# LPDDR4_SDRAM_1.net
KiCad netlist of a schematic drawn in Altium Designer
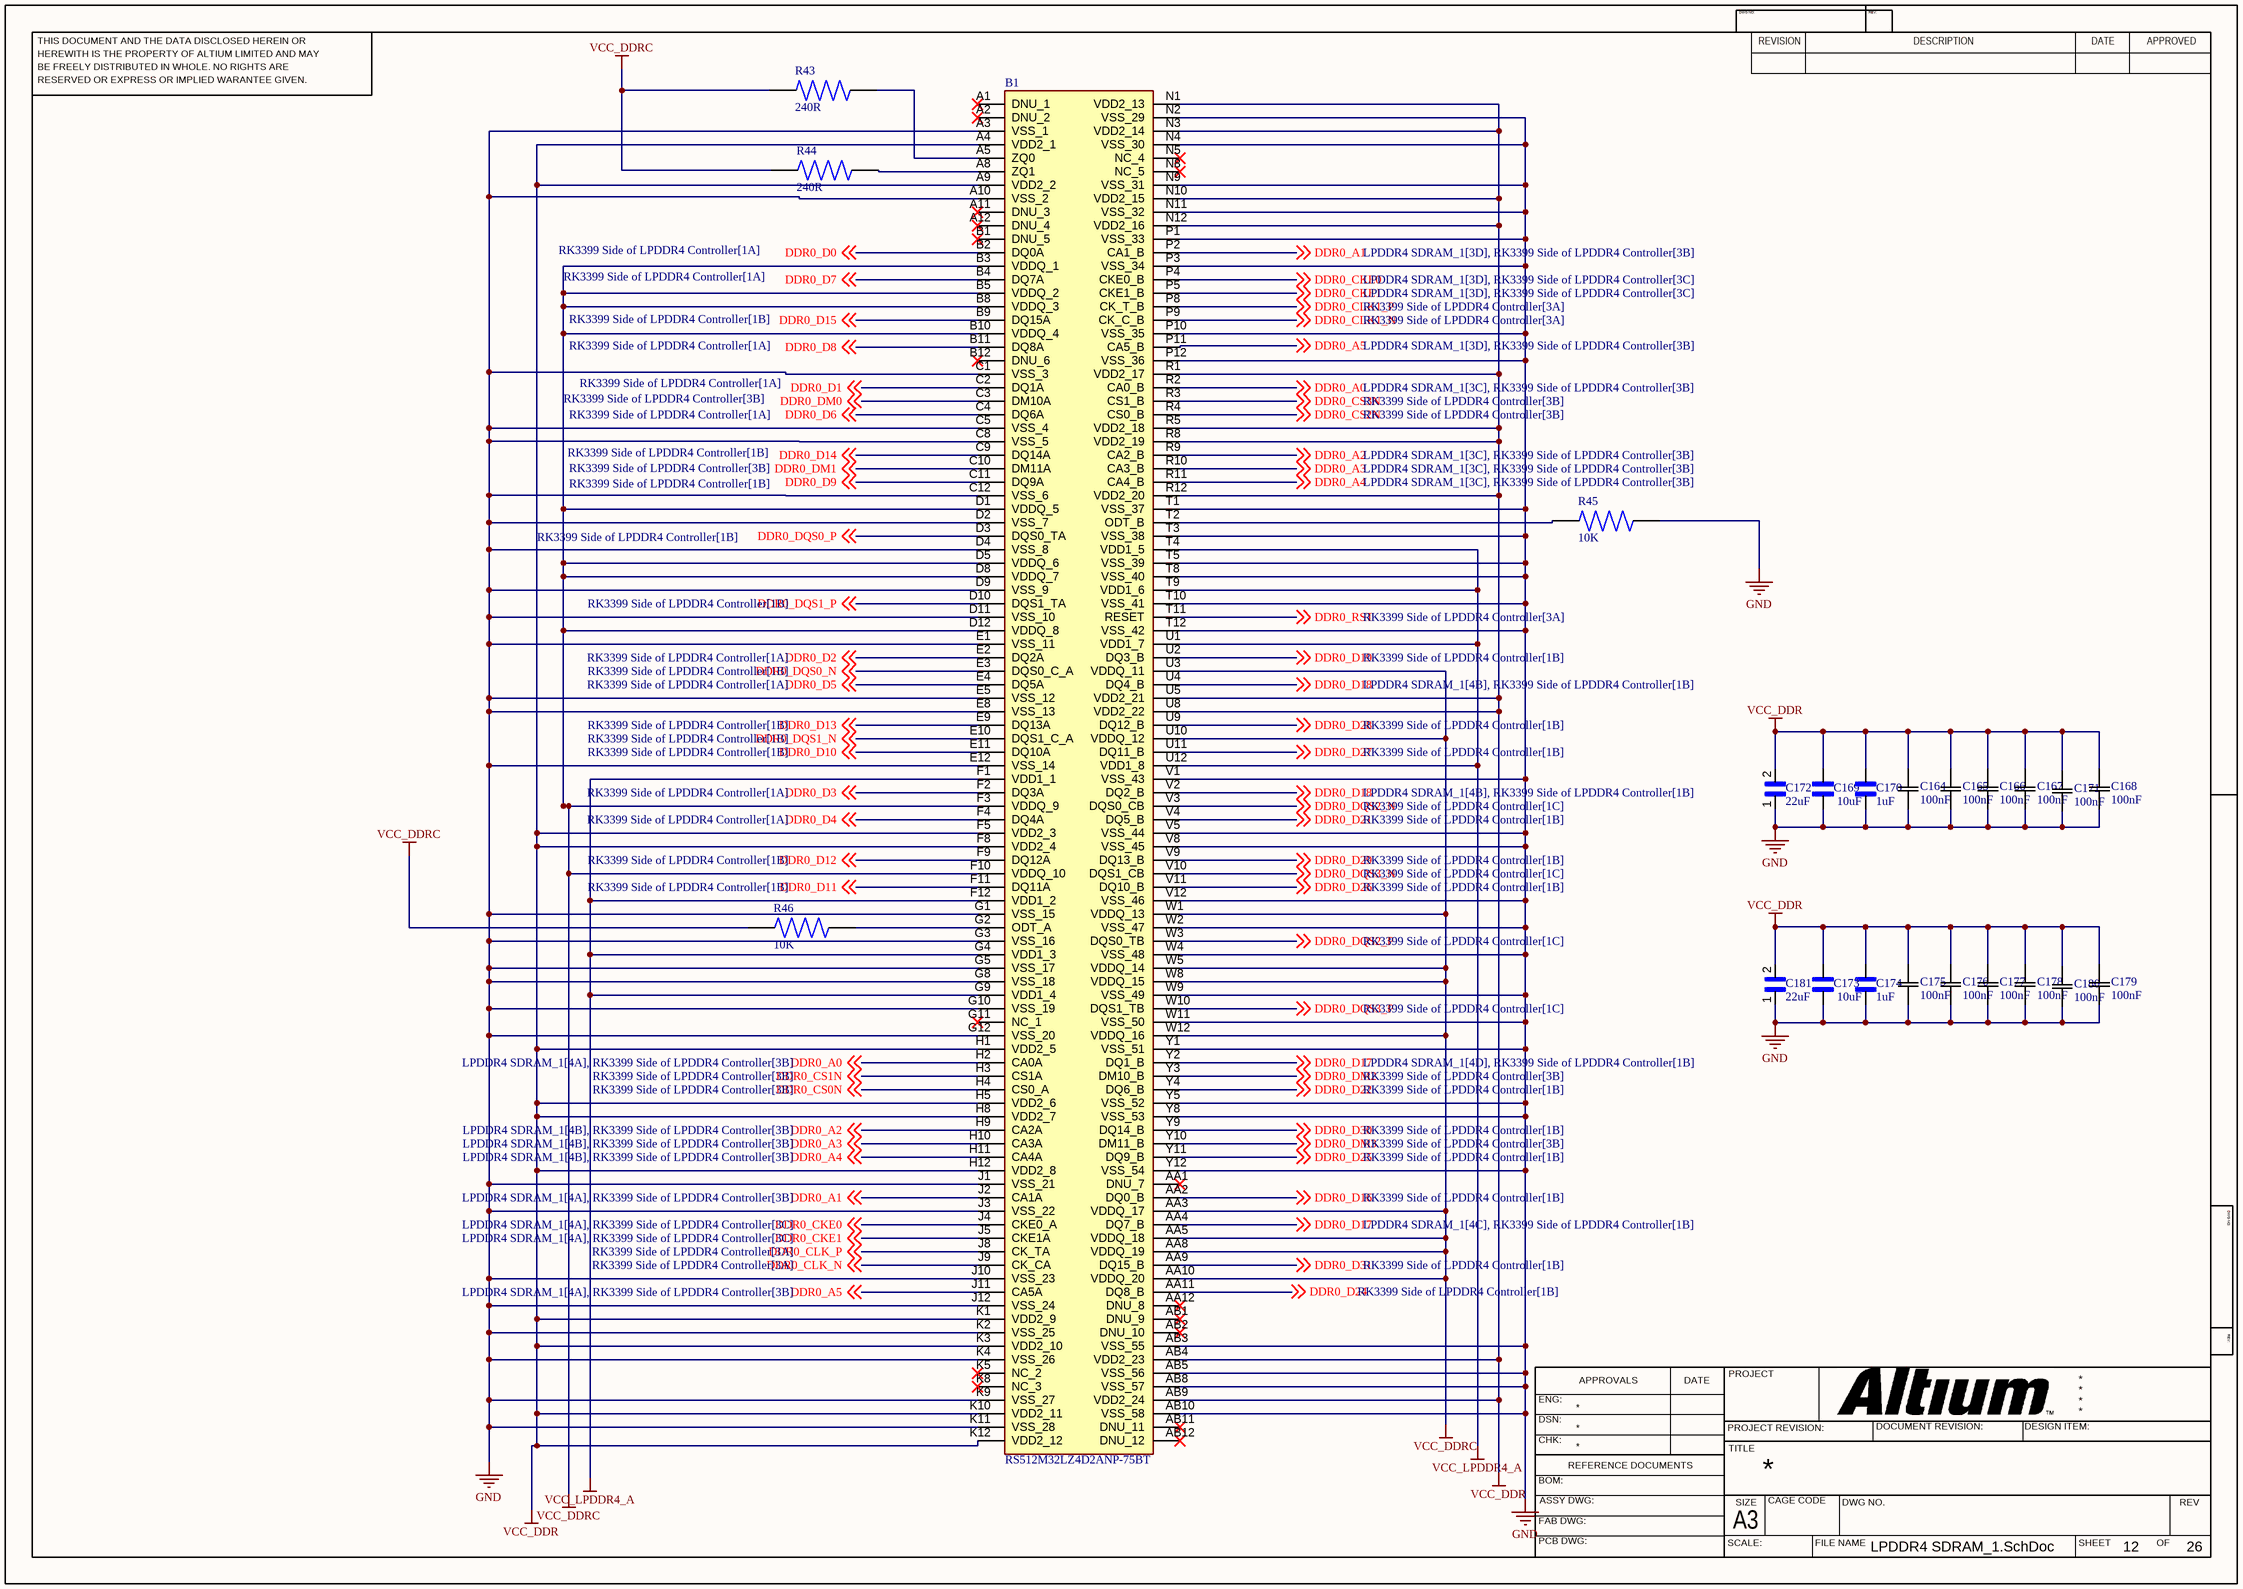
[diagram p0: LPDDR4 SDRAM_1.SchDoc]

(export (version "E")
  (design (tool "Eeschema 10.0.6"))
  (components
    (comp (ref "B1")
      (value "RS512M32LZ4D2ANP-75BT")
      (footprint "BGA200C65P12X22_1000X1500X100")
      (description "BGA-200 New Arrivals ROHS")
      (libsource (lib "RS512M32LZ4D2ANP-75BT") (part "RS512M32LZ4D2ANP-75BT"))
    )
    (comp (ref "C164")
      (value "100nF")
      (footprint "CAP_1005_TDK")
      (description "Description")
      (fields
        (field (name "MANUFACTURER_PART_NUMBER") "C1005X7R1H104M050BB")
        (field (name "COPYRIGHT") "Copyright (C) 2025 Ultra Librarian. All rights reserved.")
      )
      (libsource (lib "C1005X7R1H104M050BB") (part "C1005X7R1H104M050BB"))
    )
    (comp (ref "C165")
      (value "100nF")
      (footprint "CAP_1005_TDK")
      (description "Description")
      (fields
        (field (name "MANUFACTURER_PART_NUMBER") "C1005X7R1H104M050BB")
        (field (name "COPYRIGHT") "Copyright (C) 2025 Ultra Librarian. All rights reserved.")
      )
      (libsource (lib "C1005X7R1H104M050BB") (part "C1005X7R1H104M050BB"))
    )
    (comp (ref "C166")
      (value "100nF")
      (footprint "CAP_1005_TDK")
      (description "Description")
      (fields
        (field (name "MANUFACTURER_PART_NUMBER") "C1005X7R1H104M050BB")
        (field (name "COPYRIGHT") "Copyright (C) 2025 Ultra Librarian. All rights reserved.")
      )
      (libsource (lib "C1005X7R1H104M050BB") (part "C1005X7R1H104M050BB"))
    )
    (comp (ref "C167")
      (value "100nF")
      (footprint "CAP_1005_TDK")
      (description "Description")
      (fields
        (field (name "MANUFACTURER_PART_NUMBER") "C1005X7R1H104M050BB")
        (field (name "COPYRIGHT") "Copyright (C) 2025 Ultra Librarian. All rights reserved.")
      )
      (libsource (lib "C1005X7R1H104M050BB") (part "C1005X7R1H104M050BB"))
    )
    (comp (ref "C168")
      (value "100nF")
      (footprint "CAP_1005_TDK")
      (description "Description")
      (fields
        (field (name "MANUFACTURER_PART_NUMBER") "C1005X7R1H104M050BB")
        (field (name "COPYRIGHT") "Copyright (C) 2025 Ultra Librarian. All rights reserved.")
      )
      (libsource (lib "C1005X7R1H104M050BB") (part "C1005X7R1H104M050BB"))
    )
    (comp (ref "C169")
      (value "10uF")
      (footprint "CAPC1005X70N")
      (description "10 ÂµF Â±20% 6.3V Ceramic Capacitor X5R 0402 (1005 Metric)")
      (fields (field (name "MF") "Samsung") (field (name "MP") "CL05A106MQ5NUNC"))
      (libsource (lib "CL05A106MQ5NUNC") (part "CL05A106MQ5NUNC"))
    )
    (comp (ref "C170")
      (value "1uF")
      (footprint "CAPC1005X56N")
      (description "1 ÂµF Â±10% 10V Ceramic Capacitor X5R 0402 (1005 Metric)")
      (fields (field (name "MF") "AVX") (field (name "MP") "0402ZD105KAT4A"))
      (libsource (lib "0402ZD105KAT4A") (part "0402ZD105KAT4A"))
    )
    (comp (ref "C171")
      (value "100nF")
      (footprint "CAP_1005_TDK")
      (description "Description")
      (fields
        (field (name "MANUFACTURER_PART_NUMBER") "C1005X7R1H104M050BB")
        (field (name "COPYRIGHT") "Copyright (C) 2025 Ultra Librarian. All rights reserved.")
      )
      (libsource (lib "C1005X7R1H104M050BB") (part "C1005X7R1H104M050BB"))
    )
    (comp (ref "C172")
      (value "22uF")
      (footprint "CAPC6050X550N")
      (description "22ÂµF Â±20% 50V Ceramic Capacitor X7S Stacked SMD, 2 J-Lead")
      (fields (field (name "MP") "CKG57NX7S1H226M500JJ"))
      (libsource (lib "CKG57NX7S1H226M500JJ") (part "CKG57NX7S1H226M500JJ"))
    )
    (comp (ref "C173")
      (value "10uF")
      (footprint "CAPC1005X70N")
      (description "10 ÂµF Â±20% 6.3V Ceramic Capacitor X5R 0402 (1005 Metric)")
      (fields (field (name "MF") "Samsung") (field (name "MP") "CL05A106MQ5NUNC"))
      (libsource (lib "CL05A106MQ5NUNC") (part "CL05A106MQ5NUNC"))
    )
    (comp (ref "C174")
      (value "1uF")
      (footprint "CAPC1005X56N")
      (description "1 ÂµF Â±10% 10V Ceramic Capacitor X5R 0402 (1005 Metric)")
      (fields (field (name "MF") "AVX") (field (name "MP") "0402ZD105KAT4A"))
      (libsource (lib "0402ZD105KAT4A") (part "0402ZD105KAT4A"))
    )
    (comp (ref "C175")
      (value "100nF")
      (footprint "CAP_1005_TDK")
      (description "Description")
      (fields
        (field (name "MANUFACTURER_PART_NUMBER") "C1005X7R1H104M050BB")
        (field (name "COPYRIGHT") "Copyright (C) 2025 Ultra Librarian. All rights reserved.")
      )
      (libsource (lib "C1005X7R1H104M050BB") (part "C1005X7R1H104M050BB"))
    )
    (comp (ref "C176")
      (value "100nF")
      (footprint "CAP_1005_TDK")
      (description "Description")
      (fields
        (field (name "MANUFACTURER_PART_NUMBER") "C1005X7R1H104M050BB")
        (field (name "COPYRIGHT") "Copyright (C) 2025 Ultra Librarian. All rights reserved.")
      )
      (libsource (lib "C1005X7R1H104M050BB") (part "C1005X7R1H104M050BB"))
    )
    (comp (ref "C177")
      (value "100nF")
      (footprint "CAP_1005_TDK")
      (description "Description")
      (fields
        (field (name "MANUFACTURER_PART_NUMBER") "C1005X7R1H104M050BB")
        (field (name "COPYRIGHT") "Copyright (C) 2025 Ultra Librarian. All rights reserved.")
      )
      (libsource (lib "C1005X7R1H104M050BB") (part "C1005X7R1H104M050BB"))
    )
    (comp (ref "C178")
      (value "100nF")
      (footprint "CAP_1005_TDK")
      (description "Description")
      (fields
        (field (name "MANUFACTURER_PART_NUMBER") "C1005X7R1H104M050BB")
        (field (name "COPYRIGHT") "Copyright (C) 2025 Ultra Librarian. All rights reserved.")
      )
      (libsource (lib "C1005X7R1H104M050BB") (part "C1005X7R1H104M050BB"))
    )
    (comp (ref "C179")
      (value "100nF")
      (footprint "CAP_1005_TDK")
      (description "Description")
      (fields
        (field (name "MANUFACTURER_PART_NUMBER") "C1005X7R1H104M050BB")
        (field (name "COPYRIGHT") "Copyright (C) 2025 Ultra Librarian. All rights reserved.")
      )
      (libsource (lib "C1005X7R1H104M050BB") (part "C1005X7R1H104M050BB"))
    )
    (comp (ref "C180")
      (value "100nF")
      (footprint "CAP_1005_TDK")
      (description "Description")
      (fields
        (field (name "MANUFACTURER_PART_NUMBER") "C1005X7R1H104M050BB")
        (field (name "COPYRIGHT") "Copyright (C) 2025 Ultra Librarian. All rights reserved.")
      )
      (libsource (lib "C1005X7R1H104M050BB") (part "C1005X7R1H104M050BB"))
    )
    (comp (ref "C181")
      (value "22uF")
      (footprint "CAPC6050X550N")
      (description "22ÂµF Â±20% 50V Ceramic Capacitor X7S Stacked SMD, 2 J-Lead")
      (fields (field (name "MP") "CKG57NX7S1H226M500JJ"))
      (libsource (lib "CKG57NX7S1H226M500JJ") (part "CKG57NX7S1H226M500JJ"))
    )
    (comp (ref "R43")
      (value "240R")
      (footprint "RESC1608X50N")
      (fields (field (name "MP") "ERA6AED241V"))
      (libsource (lib "ERA6AED241V") (part "ERA6AED241V"))
    )
    (comp (ref "R44")
      (value "240R")
      (footprint "RESC1608X50N")
      (fields (field (name "MP") "ERA6AED241V"))
      (libsource (lib "ERA6AED241V") (part "ERA6AED241V"))
    )
    (comp (ref "R45")
      (value "10K")
      (footprint "RESC1608X55N")
      (description "1 kOhms Â±1% 0.1W, 1/10W Chip Resistor 0603 (1608 Metric) - Thick Film")
      (fields (field (name "MF") "Vishay") (field (name "MP") "CRCW06031K00FKECC"))
      (libsource (lib "CRCW06031K00FKECC") (part "CRCW06031K00FKECC"))
    )
    (comp (ref "R46")
      (value "10K")
      (footprint "RESC1608X55N")
      (description "1 kOhms Â±1% 0.1W, 1/10W Chip Resistor 0603 (1608 Metric) - Thick Film")
      (fields (field (name "MF") "Vishay") (field (name "MP") "CRCW06031K00FKECC"))
      (libsource (lib "CRCW06031K00FKECC") (part "CRCW06031K00FKECC"))
    )
  )
  (nets
    (net (code "1") (name "DDR0_A0") (class "Default")
      (node (ref "B1") (pin "H2") (pinfunction "CA0A_H2") (pintype "passive"))
      (node (ref "B1") (pin "R2") (pinfunction "CA0_B_R2") (pintype "passive"))
    )
    (net (code "2") (name "DDR0_A1") (class "Default")
      (node (ref "B1") (pin "J2") (pinfunction "CA1A_J2") (pintype "passive"))
      (node (ref "B1") (pin "P2") (pinfunction "CA1_B_P2") (pintype "passive"))
    )
    (net (code "3") (name "DDR0_A2") (class "Default")
      (node (ref "B1") (pin "H9") (pinfunction "CA2A_H9") (pintype "passive"))
      (node (ref "B1") (pin "R9") (pinfunction "CA2_B_R9") (pintype "passive"))
    )
    (net (code "4") (name "DDR0_A3") (class "Default")
      (node (ref "B1") (pin "H10") (pinfunction "CA3A_H10") (pintype "passive"))
      (node (ref "B1") (pin "R10") (pinfunction "CA3_B_R10") (pintype "passive"))
    )
    (net (code "5") (name "DDR0_A4") (class "Default")
      (node (ref "B1") (pin "H11") (pinfunction "CA4A_H11") (pintype "passive"))
      (node (ref "B1") (pin "R11") (pinfunction "CA4_B_R11") (pintype "passive"))
    )
    (net (code "6") (name "DDR0_A5") (class "Default")
      (node (ref "B1") (pin "J11") (pinfunction "CA5A_J11") (pintype "passive"))
      (node (ref "B1") (pin "P11") (pinfunction "CA5_B_P11") (pintype "passive"))
    )
    (net (code "7") (name "DDR0_CKE0") (class "Default")
      (node (ref "B1") (pin "J4") (pinfunction "CKE0_A_J4") (pintype "passive"))
      (node (ref "B1") (pin "P4") (pinfunction "CKE0_B_P4") (pintype "passive"))
    )
    (net (code "8") (name "DDR0_CKE1") (class "Default")
      (node (ref "B1") (pin "J5") (pinfunction "CKE1A_J5") (pintype "passive"))
      (node (ref "B1") (pin "P5") (pinfunction "CKE1_B_P5") (pintype "passive"))
    )
    (net (code "9") (name "DDR0_CLK1_N") (class "Default")
      (node (ref "B1") (pin "P9") (pinfunction "CK_C_B_P9") (pintype "passive"))
    )
    (net (code "10") (name "DDR0_CLK1_P") (class "Default")
      (node (ref "B1") (pin "P8") (pinfunction "CK_T_B_P8") (pintype "passive"))
    )
    (net (code "11") (name "DDR0_CLK_N") (class "Default")
      (node (ref "B1") (pin "J9") (pinfunction "CK_CA_J9") (pintype "passive"))
    )
    (net (code "12") (name "DDR0_CLK_P") (class "Default")
      (node (ref "B1") (pin "J8") (pinfunction "CK_TA_J8") (pintype "passive"))
    )
    (net (code "13") (name "DDR0_CS0N") (class "Default")
      (node (ref "B1") (pin "H4") (pinfunction "CS0_A_H4") (pintype "passive"))
    )
    (net (code "14") (name "DDR0_CS1N") (class "Default")
      (node (ref "B1") (pin "H3") (pinfunction "CS1A_H3") (pintype "passive"))
    )
    (net (code "15") (name "DDR0_CS2N") (class "Default")
      (node (ref "B1") (pin "R4") (pinfunction "CS0_B_R4") (pintype "passive"))
    )
    (net (code "16") (name "DDR0_CS3N") (class "Default")
      (node (ref "B1") (pin "R3") (pinfunction "CS1_B_R3") (pintype "passive"))
    )
    (net (code "17") (name "DDR0_D0") (class "Default")
      (node (ref "B1") (pin "B2") (pinfunction "DQ0A_B2") (pintype "passive"))
    )
    (net (code "18") (name "DDR0_D1") (class "Default")
      (node (ref "B1") (pin "C2") (pinfunction "DQ1A_C2") (pintype "passive"))
    )
    (net (code "19") (name "DDR0_D2") (class "Default")
      (node (ref "B1") (pin "E2") (pinfunction "DQ2A_E2") (pintype "passive"))
    )
    (net (code "20") (name "DDR0_D3") (class "Default")
      (node (ref "B1") (pin "F2") (pinfunction "DQ3A_F2") (pintype "passive"))
    )
    (net (code "21") (name "DDR0_D4") (class "Default")
      (node (ref "B1") (pin "F4") (pinfunction "DQ4A_F4") (pintype "passive"))
    )
    (net (code "22") (name "DDR0_D5") (class "Default")
      (node (ref "B1") (pin "E4") (pinfunction "DQ5A_E4") (pintype "passive"))
    )
    (net (code "23") (name "DDR0_D6") (class "Default")
      (node (ref "B1") (pin "C4") (pinfunction "DQ6A_C4") (pintype "passive"))
    )
    (net (code "24") (name "DDR0_D7") (class "Default")
      (node (ref "B1") (pin "B4") (pinfunction "DQ7A_B4") (pintype "passive"))
    )
    (net (code "25") (name "DDR0_D8") (class "Default")
      (node (ref "B1") (pin "B11") (pinfunction "DQ8A_B11") (pintype "passive"))
    )
    (net (code "26") (name "DDR0_D9") (class "Default")
      (node (ref "B1") (pin "C11") (pinfunction "DQ9A_C11") (pintype "passive"))
    )
    (net (code "27") (name "DDR0_D10") (class "Default")
      (node (ref "B1") (pin "E11") (pinfunction "DQ10A_E11") (pintype "passive"))
    )
    (net (code "28") (name "DDR0_D11") (class "Default")
      (node (ref "B1") (pin "F11") (pinfunction "DQ11A_F11") (pintype "passive"))
    )
    (net (code "29") (name "DDR0_D12") (class "Default")
      (node (ref "B1") (pin "F9") (pinfunction "DQ12A_F9") (pintype "passive"))
    )
    (net (code "30") (name "DDR0_D13") (class "Default")
      (node (ref "B1") (pin "E9") (pinfunction "DQ13A_E9") (pintype "passive"))
    )
    (net (code "31") (name "DDR0_D14") (class "Default")
      (node (ref "B1") (pin "C9") (pinfunction "DQ14A_C9") (pintype "passive"))
    )
    (net (code "32") (name "DDR0_D15") (class "Default")
      (node (ref "B1") (pin "B9") (pinfunction "DQ15A_B9") (pintype "passive"))
    )
    (net (code "33") (name "DDR0_D16") (class "Default")
      (node (ref "B1") (pin "AA2") (pinfunction "DQ0_B_AA2") (pintype "passive"))
    )
    (net (code "34") (name "DDR0_D17") (class "Default")
      (node (ref "B1") (pin "AA4") (pinfunction "DQ7_B_AA4") (pintype "passive"))
      (node (ref "B1") (pin "Y2") (pinfunction "DQ1_B_Y2") (pintype "passive"))
    )
    (net (code "35") (name "DDR0_D18") (class "Default")
      (node (ref "B1") (pin "U4") (pinfunction "DQ4_B_U4") (pintype "passive"))
      (node (ref "B1") (pin "V2") (pinfunction "DQ2_B_V2") (pintype "passive"))
    )
    (net (code "36") (name "DDR0_D19") (class "Default")
      (node (ref "B1") (pin "U2") (pinfunction "DQ3_B_U2") (pintype "passive"))
    )
    (net (code "37") (name "DDR0_D21") (class "Default")
      (node (ref "B1") (pin "V4") (pinfunction "DQ5_B_V4") (pintype "passive"))
    )
    (net (code "38") (name "DDR0_D22") (class "Default")
      (node (ref "B1") (pin "Y4") (pinfunction "DQ6_B_Y4") (pintype "passive"))
    )
    (net (code "39") (name "DDR0_D24") (class "Default")
      (node (ref "B1") (pin "AA11") (pinfunction "DQ8_B_AA11") (pintype "passive"))
    )
    (net (code "40") (name "DDR0_D25") (class "Default")
      (node (ref "B1") (pin "Y11") (pinfunction "DQ9_B_Y11") (pintype "passive"))
    )
    (net (code "41") (name "DDR0_D26") (class "Default")
      (node (ref "B1") (pin "V11") (pinfunction "DQ10_B_V11") (pintype "passive"))
    )
    (net (code "42") (name "DDR0_D27") (class "Default")
      (node (ref "B1") (pin "U11") (pinfunction "DQ11_B_U11") (pintype "passive"))
    )
    (net (code "43") (name "DDR0_D28") (class "Default")
      (node (ref "B1") (pin "U9") (pinfunction "DQ12_B_U9") (pintype "passive"))
    )
    (net (code "44") (name "DDR0_D29") (class "Default")
      (node (ref "B1") (pin "V9") (pinfunction "DQ13_B_V9") (pintype "passive"))
    )
    (net (code "45") (name "DDR0_D30") (class "Default")
      (node (ref "B1") (pin "Y9") (pinfunction "DQ14_B_Y9") (pintype "passive"))
    )
    (net (code "46") (name "DDR0_D31") (class "Default")
      (node (ref "B1") (pin "AA9") (pinfunction "DQ15_B_AA9") (pintype "passive"))
    )
    (net (code "47") (name "DDR0_DM0") (class "Default")
      (node (ref "B1") (pin "C3") (pinfunction "DM10A_C3") (pintype "passive"))
    )
    (net (code "48") (name "DDR0_DM1") (class "Default")
      (node (ref "B1") (pin "C10") (pinfunction "DM11A_C10") (pintype "passive"))
    )
    (net (code "49") (name "DDR0_DM2") (class "Default")
      (node (ref "B1") (pin "Y3") (pinfunction "DM10_B_Y3") (pintype "passive"))
    )
    (net (code "50") (name "DDR0_DM3") (class "Default")
      (node (ref "B1") (pin "Y10") (pinfunction "DM11_B_Y10") (pintype "passive"))
    )
    (net (code "51") (name "DDR0_DQS0_N") (class "Default")
      (node (ref "B1") (pin "E3") (pinfunction "DQS0_C_A_E3") (pintype "passive"))
    )
    (net (code "52") (name "DDR0_DQS0_P") (class "Default")
      (node (ref "B1") (pin "D3") (pinfunction "DQS0_TA_D3") (pintype "passive"))
    )
    (net (code "53") (name "DDR0_DQS1_N") (class "Default")
      (node (ref "B1") (pin "E10") (pinfunction "DQS1_C_A_E10") (pintype "passive"))
    )
    (net (code "54") (name "DDR0_DQS1_P") (class "Default")
      (node (ref "B1") (pin "D10") (pinfunction "DQS1_TA_D10") (pintype "passive"))
    )
    (net (code "55") (name "DDR0_DQS2_N") (class "Default")
      (node (ref "B1") (pin "V3") (pinfunction "DQS0_CB_V3") (pintype "passive"))
    )
    (net (code "56") (name "DDR0_DQS2_P") (class "Default")
      (node (ref "B1") (pin "W3") (pinfunction "DQS0_TB_W3") (pintype "passive"))
    )
    (net (code "57") (name "DDR0_DQS3_N") (class "Default")
      (node (ref "B1") (pin "V10") (pinfunction "DQS1_CB_V10") (pintype "passive"))
    )
    (net (code "58") (name "DDR0_DQS3_P") (class "Default")
      (node (ref "B1") (pin "W10") (pinfunction "DQS1_TB_W10") (pintype "passive"))
    )
    (net (code "59") (name "DDR0_RST") (class "Default")
      (node (ref "B1") (pin "T11") (pinfunction "RESET_T11") (pintype "passive"))
    )
    (net (code "60") (name "GND") (class "Default")
      (node (ref "B1") (pin "A10") (pinfunction "VSS_2_A10") (pintype "passive"))
      (node (ref "B1") (pin "A3") (pinfunction "VSS_1_A3") (pintype "passive"))
      (node (ref "B1") (pin "AB10") (pinfunction "VSS_58_AB10") (pintype "passive"))
      (node (ref "B1") (pin "AB3") (pinfunction "VSS_55_AB3") (pintype "passive"))
      (node (ref "B1") (pin "AB5") (pinfunction "VSS_56_AB5") (pintype "passive"))
      (node (ref "B1") (pin "AB8") (pinfunction "VSS_57_AB8") (pintype "passive"))
      (node (ref "B1") (pin "C1") (pinfunction "VSS_3_C1") (pintype "passive"))
      (node (ref "B1") (pin "C12") (pinfunction "VSS_6_C12") (pintype "passive"))
      (node (ref "B1") (pin "C5") (pinfunction "VSS_4_C5") (pintype "passive"))
      (node (ref "B1") (pin "C8") (pinfunction "VSS_5_C8") (pintype "passive"))
      (node (ref "B1") (pin "D11") (pinfunction "VSS_10_D11") (pintype "passive"))
      (node (ref "B1") (pin "D2") (pinfunction "VSS_7_D2") (pintype "passive"))
      (node (ref "B1") (pin "D4") (pinfunction "VSS_8_D4") (pintype "passive"))
      (node (ref "B1") (pin "D9") (pinfunction "VSS_9_D9") (pintype "passive"))
      (node (ref "B1") (pin "E1") (pinfunction "VSS_11_E1") (pintype "passive"))
      (node (ref "B1") (pin "E12") (pinfunction "VSS_14_E12") (pintype "passive"))
      (node (ref "B1") (pin "E5") (pinfunction "VSS_12_E5") (pintype "passive"))
      (node (ref "B1") (pin "E8") (pinfunction "VSS_13_E8") (pintype "passive"))
      (node (ref "B1") (pin "G1") (pinfunction "VSS_15_G1") (pintype "passive"))
      (node (ref "B1") (pin "G10") (pinfunction "VSS_19_G10") (pintype "passive"))
      (node (ref "B1") (pin "G12") (pinfunction "VSS_20_G12") (pintype "passive"))
      (node (ref "B1") (pin "G3") (pinfunction "VSS_16_G3") (pintype "passive"))
      (node (ref "B1") (pin "G5") (pinfunction "VSS_17_G5") (pintype "passive"))
      (node (ref "B1") (pin "G8") (pinfunction "VSS_18_G8") (pintype "passive"))
      (node (ref "B1") (pin "J1") (pinfunction "VSS_21_J1") (pintype "passive"))
      (node (ref "B1") (pin "J10") (pinfunction "VSS_23_J10") (pintype "passive"))
      (node (ref "B1") (pin "J12") (pinfunction "VSS_24_J12") (pintype "passive"))
      (node (ref "B1") (pin "J3") (pinfunction "VSS_22_J3") (pintype "passive"))
      (node (ref "B1") (pin "K11") (pinfunction "VSS_28_K11") (pintype "passive"))
      (node (ref "B1") (pin "K2") (pinfunction "VSS_25_K2") (pintype "passive"))
      (node (ref "B1") (pin "K4") (pinfunction "VSS_26_K4") (pintype "passive"))
      (node (ref "B1") (pin "K9") (pinfunction "VSS_27_K9") (pintype "passive"))
      (node (ref "B1") (pin "N11") (pinfunction "VSS_32_N11") (pintype "passive"))
      (node (ref "B1") (pin "N2") (pinfunction "VSS_29_N2") (pintype "passive"))
      (node (ref "B1") (pin "N4") (pinfunction "VSS_30_N4") (pintype "passive"))
      (node (ref "B1") (pin "N9") (pinfunction "VSS_31_N9") (pintype "passive"))
      (node (ref "B1") (pin "P1") (pinfunction "VSS_33_P1") (pintype "passive"))
      (node (ref "B1") (pin "P10") (pinfunction "VSS_35_P10") (pintype "passive"))
      (node (ref "B1") (pin "P12") (pinfunction "VSS_36_P12") (pintype "passive"))
      (node (ref "B1") (pin "P3") (pinfunction "VSS_34_P3") (pintype "passive"))
      (node (ref "B1") (pin "T1") (pinfunction "VSS_37_T1") (pintype "passive"))
      (node (ref "B1") (pin "T10") (pinfunction "VSS_41_T10") (pintype "passive"))
      (node (ref "B1") (pin "T12") (pinfunction "VSS_42_T12") (pintype "passive"))
      (node (ref "B1") (pin "T3") (pinfunction "VSS_38_T3") (pintype "passive"))
      (node (ref "B1") (pin "T5") (pinfunction "VSS_39_T5") (pintype "passive"))
      (node (ref "B1") (pin "T8") (pinfunction "VSS_40_T8") (pintype "passive"))
      (node (ref "B1") (pin "V1") (pinfunction "VSS_43_V1") (pintype "passive"))
      (node (ref "B1") (pin "V12") (pinfunction "VSS_46_V12") (pintype "passive"))
      (node (ref "B1") (pin "V5") (pinfunction "VSS_44_V5") (pintype "passive"))
      (node (ref "B1") (pin "V8") (pinfunction "VSS_45_V8") (pintype "passive"))
      (node (ref "B1") (pin "W11") (pinfunction "VSS_50_W11") (pintype "passive"))
      (node (ref "B1") (pin "W2") (pinfunction "VSS_47_W2") (pintype "passive"))
      (node (ref "B1") (pin "W4") (pinfunction "VSS_48_W4") (pintype "passive"))
      (node (ref "B1") (pin "W9") (pinfunction "VSS_49_W9") (pintype "passive"))
      (node (ref "B1") (pin "Y1") (pinfunction "VSS_51_Y1") (pintype "passive"))
      (node (ref "B1") (pin "Y12") (pinfunction "VSS_54_Y12") (pintype "passive"))
      (node (ref "B1") (pin "Y5") (pinfunction "VSS_52_Y5") (pintype "passive"))
      (node (ref "B1") (pin "Y8") (pinfunction "VSS_53_Y8") (pintype "passive"))
      (node (ref "C164") (pin "1") (pinfunction "1_1") (pintype "passive"))
      (node (ref "C165") (pin "1") (pinfunction "1_1") (pintype "passive"))
      (node (ref "C166") (pin "1") (pinfunction "1_1") (pintype "passive"))
      (node (ref "C167") (pin "1") (pinfunction "1_1") (pintype "passive"))
      (node (ref "C168") (pin "1") (pinfunction "1_1") (pintype "passive"))
      (node (ref "C169") (pin "1") (pinfunction "1_1") (pintype "passive"))
      (node (ref "C170") (pin "1") (pinfunction "1_1") (pintype "passive"))
      (node (ref "C171") (pin "1") (pinfunction "1_1") (pintype "passive"))
      (node (ref "C172") (pin "1") (pinfunction "1_1") (pintype "passive"))
      (node (ref "C173") (pin "1") (pinfunction "1_1") (pintype "passive"))
      (node (ref "C174") (pin "1") (pinfunction "1_1") (pintype "passive"))
      (node (ref "C175") (pin "1") (pinfunction "1_1") (pintype "passive"))
      (node (ref "C176") (pin "1") (pinfunction "1_1") (pintype "passive"))
      (node (ref "C177") (pin "1") (pinfunction "1_1") (pintype "passive"))
      (node (ref "C178") (pin "1") (pinfunction "1_1") (pintype "passive"))
      (node (ref "C179") (pin "1") (pinfunction "1_1") (pintype "passive"))
      (node (ref "C180") (pin "1") (pinfunction "1_1") (pintype "passive"))
      (node (ref "C181") (pin "1") (pinfunction "1_1") (pintype "passive"))
      (node (ref "R45") (pin "2") (pinfunction "2_2") (pintype "passive"))
    )
    (net (code "61") (name "Net-(B1-ODT_A)") (class "Default")
      (node (ref "B1") (pin "G2") (pinfunction "ODT_A_G2") (pintype "passive"))
      (node (ref "R46") (pin "1") (pinfunction "1_1") (pintype "passive"))
    )
    (net (code "62") (name "Net-(B1-ODT_B)") (class "Default")
      (node (ref "B1") (pin "T2") (pinfunction "ODT_B_T2") (pintype "passive"))
      (node (ref "R45") (pin "1") (pinfunction "1_1") (pintype "passive"))
    )
    (net (code "63") (name "Net-(B1-ZQ0)") (class "Default")
      (node (ref "B1") (pin "A5") (pinfunction "ZQ0_A5") (pintype "passive"))
      (node (ref "R43") (pin "2") (pinfunction "2_2") (pintype "passive"))
    )
    (net (code "64") (name "Net-(B1-ZQ1)") (class "Default")
      (node (ref "B1") (pin "A8") (pinfunction "ZQ1_A8") (pintype "passive"))
      (node (ref "R44") (pin "2") (pinfunction "2_2") (pintype "passive"))
    )
    (net (code "65") (name "VCC_DDR") (class "Default")
      (node (ref "B1") (pin "A4") (pinfunction "VDD2_1_A4") (pintype "passive"))
      (node (ref "B1") (pin "A9") (pinfunction "VDD2_2_A9") (pintype "passive"))
      (node (ref "B1") (pin "AB4") (pinfunction "VDD2_23_AB4") (pintype "passive"))
      (node (ref "B1") (pin "AB9") (pinfunction "VDD2_24_AB9") (pintype "passive"))
      (node (ref "B1") (pin "F5") (pinfunction "VDD2_3_F5") (pintype "passive"))
      (node (ref "B1") (pin "F8") (pinfunction "VDD2_4_F8") (pintype "passive"))
      (node (ref "B1") (pin "H1") (pinfunction "VDD2_5_H1") (pintype "passive"))
      (node (ref "B1") (pin "H12") (pinfunction "VDD2_8_H12") (pintype "passive"))
      (node (ref "B1") (pin "H5") (pinfunction "VDD2_6_H5") (pintype "passive"))
      (node (ref "B1") (pin "H8") (pinfunction "VDD2_7_H8") (pintype "passive"))
      (node (ref "B1") (pin "K1") (pinfunction "VDD2_9_K1") (pintype "passive"))
      (node (ref "B1") (pin "K10") (pinfunction "VDD2_11_K10") (pintype "passive"))
      (node (ref "B1") (pin "K12") (pinfunction "VDD2_12_K12") (pintype "passive"))
      (node (ref "B1") (pin "K3") (pinfunction "VDD2_10_K3") (pintype "passive"))
      (node (ref "B1") (pin "N1") (pinfunction "VDD2_13_N1") (pintype "passive"))
      (node (ref "B1") (pin "N10") (pinfunction "VDD2_15_N10") (pintype "passive"))
      (node (ref "B1") (pin "N12") (pinfunction "VDD2_16_N12") (pintype "passive"))
      (node (ref "B1") (pin "N3") (pinfunction "VDD2_14_N3") (pintype "passive"))
      (node (ref "B1") (pin "R1") (pinfunction "VDD2_17_R1") (pintype "passive"))
      (node (ref "B1") (pin "R12") (pinfunction "VDD2_20_R12") (pintype "passive"))
      (node (ref "B1") (pin "R5") (pinfunction "VDD2_18_R5") (pintype "passive"))
      (node (ref "B1") (pin "R8") (pinfunction "VDD2_19_R8") (pintype "passive"))
      (node (ref "B1") (pin "U5") (pinfunction "VDD2_21_U5") (pintype "passive"))
      (node (ref "B1") (pin "U8") (pinfunction "VDD2_22_U8") (pintype "passive"))
      (node (ref "C164") (pin "2") (pinfunction "2_2") (pintype "passive"))
      (node (ref "C165") (pin "2") (pinfunction "2_2") (pintype "passive"))
      (node (ref "C166") (pin "2") (pinfunction "2_2") (pintype "passive"))
      (node (ref "C167") (pin "2") (pinfunction "2_2") (pintype "passive"))
      (node (ref "C168") (pin "2") (pinfunction "2_2") (pintype "passive"))
      (node (ref "C169") (pin "2") (pinfunction "2_2") (pintype "passive"))
      (node (ref "C170") (pin "2") (pinfunction "2_2") (pintype "passive"))
      (node (ref "C171") (pin "2") (pinfunction "2_2") (pintype "passive"))
      (node (ref "C172") (pin "2") (pinfunction "2_2") (pintype "passive"))
      (node (ref "C173") (pin "2") (pinfunction "2_2") (pintype "passive"))
      (node (ref "C174") (pin "2") (pinfunction "2_2") (pintype "passive"))
      (node (ref "C175") (pin "2") (pinfunction "2_2") (pintype "passive"))
      (node (ref "C176") (pin "2") (pinfunction "2_2") (pintype "passive"))
      (node (ref "C177") (pin "2") (pinfunction "2_2") (pintype "passive"))
      (node (ref "C178") (pin "2") (pinfunction "2_2") (pintype "passive"))
      (node (ref "C179") (pin "2") (pinfunction "2_2") (pintype "passive"))
      (node (ref "C180") (pin "2") (pinfunction "2_2") (pintype "passive"))
      (node (ref "C181") (pin "2") (pinfunction "2_2") (pintype "passive"))
    )
    (net (code "66") (name "VCC_DDRC") (class "Default")
      (node (ref "B1") (pin "AA10") (pinfunction "VDDQ_20_AA10") (pintype "passive"))
      (node (ref "B1") (pin "AA3") (pinfunction "VDDQ_17_AA3") (pintype "passive"))
      (node (ref "B1") (pin "AA5") (pinfunction "VDDQ_18_AA5") (pintype "passive"))
      (node (ref "B1") (pin "AA8") (pinfunction "VDDQ_19_AA8") (pintype "passive"))
      (node (ref "B1") (pin "B10") (pinfunction "VDDQ_4_B10") (pintype "passive"))
      (node (ref "B1") (pin "B3") (pinfunction "VDDQ_1_B3") (pintype "passive"))
      (node (ref "B1") (pin "B5") (pinfunction "VDDQ_2_B5") (pintype "passive"))
      (node (ref "B1") (pin "B8") (pinfunction "VDDQ_3_B8") (pintype "passive"))
      (node (ref "B1") (pin "D1") (pinfunction "VDDQ_5_D1") (pintype "passive"))
      (node (ref "B1") (pin "D12") (pinfunction "VDDQ_8_D12") (pintype "passive"))
      (node (ref "B1") (pin "D5") (pinfunction "VDDQ_6_D5") (pintype "passive"))
      (node (ref "B1") (pin "D8") (pinfunction "VDDQ_7_D8") (pintype "passive"))
      (node (ref "B1") (pin "F10") (pinfunction "VDDQ_10_F10") (pintype "passive"))
      (node (ref "B1") (pin "F3") (pinfunction "VDDQ_9_F3") (pintype "passive"))
      (node (ref "B1") (pin "U10") (pinfunction "VDDQ_12_U10") (pintype "passive"))
      (node (ref "B1") (pin "U3") (pinfunction "VDDQ_11_U3") (pintype "passive"))
      (node (ref "B1") (pin "W1") (pinfunction "VDDQ_13_W1") (pintype "passive"))
      (node (ref "B1") (pin "W12") (pinfunction "VDDQ_16_W12") (pintype "passive"))
      (node (ref "B1") (pin "W5") (pinfunction "VDDQ_14_W5") (pintype "passive"))
      (node (ref "B1") (pin "W8") (pinfunction "VDDQ_15_W8") (pintype "passive"))
      (node (ref "R43") (pin "1") (pinfunction "1_1") (pintype "passive"))
      (node (ref "R44") (pin "1") (pinfunction "1_1") (pintype "passive"))
      (node (ref "R46") (pin "2") (pinfunction "2_2") (pintype "passive"))
    )
    (net (code "67") (name "VCC_LPDDR4_A") (class "Default")
      (node (ref "B1") (pin "F1") (pinfunction "VDD1_1_F1") (pintype "passive"))
      (node (ref "B1") (pin "F12") (pinfunction "VDD1_2_F12") (pintype "passive"))
      (node (ref "B1") (pin "G4") (pinfunction "VDD1_3_G4") (pintype "passive"))
      (node (ref "B1") (pin "G9") (pinfunction "VDD1_4_G9") (pintype "passive"))
      (node (ref "B1") (pin "T4") (pinfunction "VDD1_5_T4") (pintype "passive"))
      (node (ref "B1") (pin "T9") (pinfunction "VDD1_6_T9") (pintype "passive"))
      (node (ref "B1") (pin "U1") (pinfunction "VDD1_7_U1") (pintype "passive"))
      (node (ref "B1") (pin "U12") (pinfunction "VDD1_8_U12") (pintype "passive"))
    )
    (net (code "68") (name "unconnected-(B1-DNU_1-PadA1)") (class "Default")
      (node (ref "B1") (pin "A1") (pinfunction "DNU_1_A1") (pintype "passive+no_connect"))
    )
    (net (code "69") (name "unconnected-(B1-DNU_2-PadA2)") (class "Default")
      (node (ref "B1") (pin "A2") (pinfunction "DNU_2_A2") (pintype "passive+no_connect"))
    )
    (net (code "70") (name "unconnected-(B1-DNU_3-PadA11)") (class "Default")
      (node (ref "B1") (pin "A11") (pinfunction "DNU_3_A11") (pintype "passive+no_connect"))
    )
    (net (code "71") (name "unconnected-(B1-DNU_4-PadA12)") (class "Default")
      (node (ref "B1") (pin "A12") (pinfunction "DNU_4_A12") (pintype "passive+no_connect"))
    )
    (net (code "72") (name "unconnected-(B1-DNU_5-PadB1)") (class "Default")
      (node (ref "B1") (pin "B1") (pinfunction "DNU_5_B1") (pintype "passive+no_connect"))
    )
    (net (code "73") (name "unconnected-(B1-DNU_6-PadB12)") (class "Default")
      (node (ref "B1") (pin "B12") (pinfunction "DNU_6_B12") (pintype "passive+no_connect"))
    )
    (net (code "74") (name "unconnected-(B1-DNU_7-PadAA1)") (class "Default")
      (node (ref "B1") (pin "AA1") (pinfunction "DNU_7_AA1") (pintype "passive+no_connect"))
    )
    (net (code "75") (name "unconnected-(B1-DNU_8-PadAA12)") (class "Default")
      (node (ref "B1") (pin "AA12") (pinfunction "DNU_8_AA12") (pintype "passive+no_connect"))
    )
    (net (code "76") (name "unconnected-(B1-DNU_9-PadAB1)") (class "Default")
      (node (ref "B1") (pin "AB1") (pinfunction "DNU_9_AB1") (pintype "passive+no_connect"))
    )
    (net (code "77") (name "unconnected-(B1-DNU_10-PadAB2)") (class "Default")
      (node (ref "B1") (pin "AB2") (pinfunction "DNU_10_AB2") (pintype "passive+no_connect"))
    )
    (net (code "78") (name "unconnected-(B1-DNU_11-PadAB11)") (class "Default")
      (node (ref "B1") (pin "AB11") (pinfunction "DNU_11_AB11") (pintype "passive+no_connect"))
    )
    (net (code "79") (name "unconnected-(B1-DNU_12-PadAB12)") (class "Default")
      (node (ref "B1") (pin "AB12") (pinfunction "DNU_12_AB12") (pintype "passive+no_connect"))
    )
    (net (code "80") (name "unconnected-(B1-NC_1-PadG11)") (class "Default")
      (node (ref "B1") (pin "G11") (pinfunction "NC_1_G11") (pintype "passive+no_connect"))
    )
    (net (code "81") (name "unconnected-(B1-NC_2-PadK5)") (class "Default")
      (node (ref "B1") (pin "K5") (pinfunction "NC_2_K5") (pintype "passive+no_connect"))
    )
    (net (code "82") (name "unconnected-(B1-NC_3-PadK8)") (class "Default")
      (node (ref "B1") (pin "K8") (pinfunction "NC_3_K8") (pintype "passive+no_connect"))
    )
    (net (code "83") (name "unconnected-(B1-NC_4-PadN5)") (class "Default")
      (node (ref "B1") (pin "N5") (pinfunction "NC_4_N5") (pintype "passive+no_connect"))
    )
    (net (code "84") (name "unconnected-(B1-NC_5-PadN8)") (class "Default")
      (node (ref "B1") (pin "N8") (pinfunction "NC_5_N8") (pintype "passive+no_connect"))
    )
  )
)
